# bot_schem_rev1.net
KiCad netlist of a schematic drawn in Altium Designer
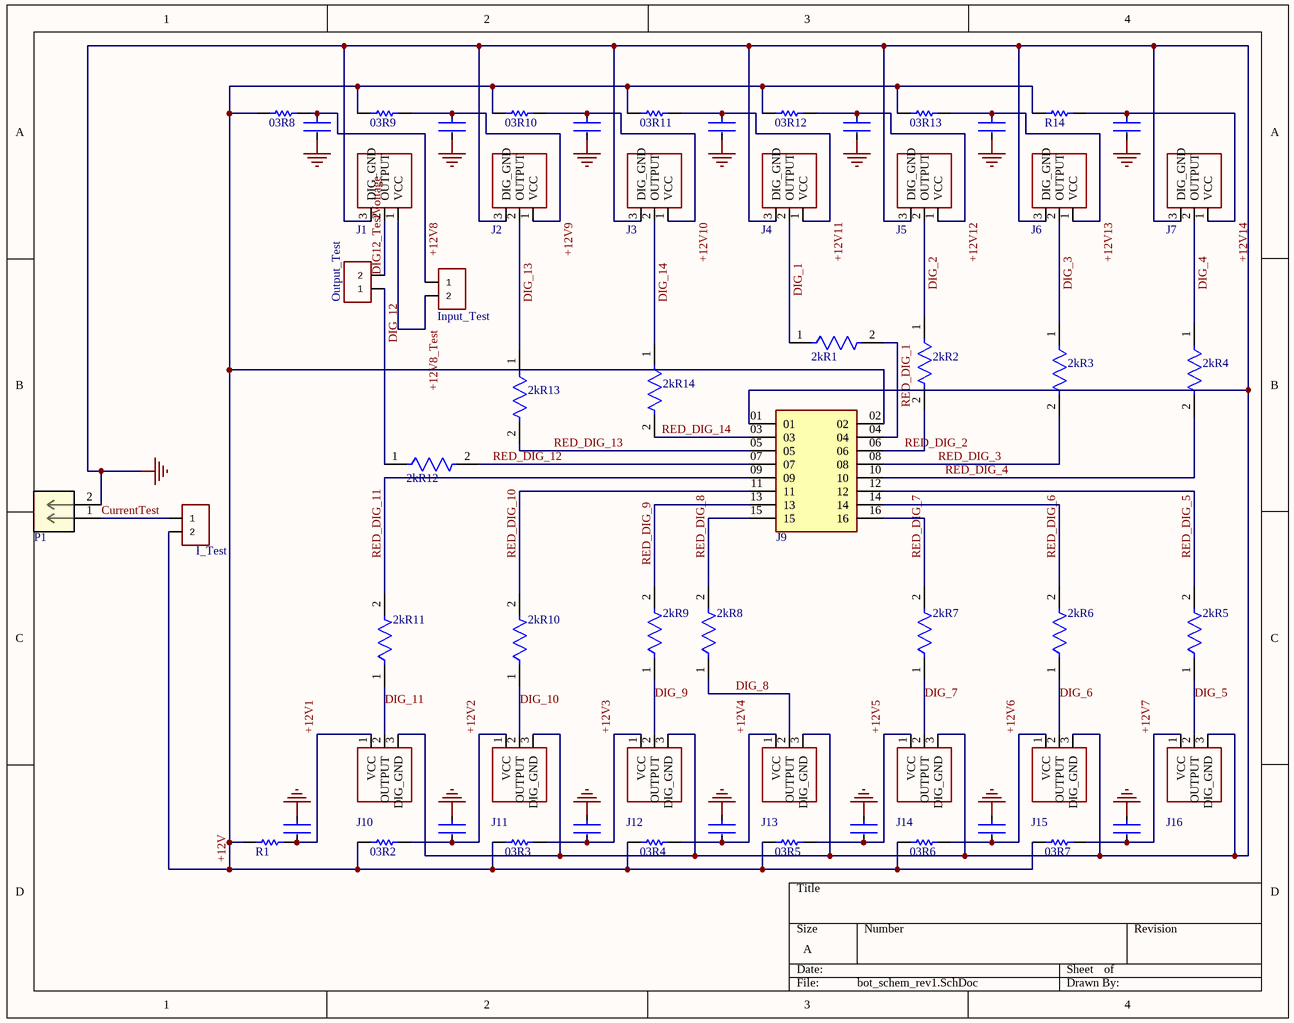
[diagram p0: bot_schem_rev1.SchDoc]

(export (version "E")
  (design (tool "Eeschema 10.0.6"))
  (components
    (comp (ref "2kR1")
      (value "CRCW06031K80FKEA")
      (footprint "2kOhm")
      (description "Res Thick Film 0603 1.8K Ohm 1% 1/10W ±100ppm/°C Molded SMD Paper T/R")
      (fields (field (name "MANUFACTURER") "Vishay") (field (name "TOLERANCE") "1%"))
      (libsource (lib "ps_schlib") (part "CRCW06031K80FKEA"))
    )
    (comp (ref "2kR2")
      (value "CRCW06031K80FKEA")
      (footprint "2kOhm")
      (description "Res Thick Film 0603 1.8K Ohm 1% 1/10W ±100ppm/°C Molded SMD Paper T/R")
      (fields (field (name "MANUFACTURER") "Vishay") (field (name "TOLERANCE") "1%"))
      (libsource (lib "ps_schlib") (part "CRCW06031K80FKEA"))
    )
    (comp (ref "2kR3")
      (value "CRCW06031K80FKEA")
      (footprint "2kOhm")
      (description "Res Thick Film 0603 1.8K Ohm 1% 1/10W ±100ppm/°C Molded SMD Paper T/R")
      (fields (field (name "MANUFACTURER") "Vishay") (field (name "TOLERANCE") "1%"))
      (libsource (lib "ps_schlib") (part "CRCW06031K80FKEA"))
    )
    (comp (ref "2kR4")
      (value "CRCW06031K80FKEA")
      (footprint "2kOhm")
      (description "Res Thick Film 0603 1.8K Ohm 1% 1/10W ±100ppm/°C Molded SMD Paper T/R")
      (fields (field (name "MANUFACTURER") "Vishay") (field (name "TOLERANCE") "1%"))
      (libsource (lib "ps_schlib") (part "CRCW06031K80FKEA"))
    )
    (comp (ref "2kR5")
      (value "CRCW06031K80FKEA")
      (footprint "2kOhm")
      (description "Res Thick Film 0603 1.8K Ohm 1% 1/10W ±100ppm/°C Molded SMD Paper T/R")
      (fields (field (name "MANUFACTURER") "Vishay") (field (name "TOLERANCE") "1%"))
      (libsource (lib "ps_schlib") (part "CRCW06031K80FKEA"))
    )
    (comp (ref "2kR6")
      (value "CRCW06031K80FKEA")
      (footprint "2kOhm")
      (description "Res Thick Film 0603 1.8K Ohm 1% 1/10W ±100ppm/°C Molded SMD Paper T/R")
      (fields (field (name "MANUFACTURER") "Vishay") (field (name "TOLERANCE") "1%"))
      (libsource (lib "ps_schlib") (part "CRCW06031K80FKEA"))
    )
    (comp (ref "2kR7")
      (value "CRCW06031K80FKEA")
      (footprint "2kOhm")
      (description "Res Thick Film 0603 1.8K Ohm 1% 1/10W ±100ppm/°C Molded SMD Paper T/R")
      (fields (field (name "MANUFACTURER") "Vishay") (field (name "TOLERANCE") "1%"))
      (libsource (lib "ps_schlib") (part "CRCW06031K80FKEA"))
    )
    (comp (ref "2kR8")
      (value "CRCW06031K80FKEA")
      (footprint "2kOhm")
      (description "Res Thick Film 0603 1.8K Ohm 1% 1/10W ±100ppm/°C Molded SMD Paper T/R")
      (fields (field (name "MANUFACTURER") "Vishay") (field (name "TOLERANCE") "1%"))
      (libsource (lib "ps_schlib") (part "CRCW06031K80FKEA"))
    )
    (comp (ref "2kR9")
      (value "CRCW06031K80FKEA")
      (footprint "2kOhm")
      (description "Res Thick Film 0603 1.8K Ohm 1% 1/10W ±100ppm/°C Molded SMD Paper T/R")
      (fields (field (name "MANUFACTURER") "Vishay") (field (name "TOLERANCE") "1%"))
      (libsource (lib "ps_schlib") (part "CRCW06031K80FKEA"))
    )
    (comp (ref "2kR10")
      (value "CRCW06031K80FKEA")
      (footprint "2kOhm")
      (description "Res Thick Film 0603 1.8K Ohm 1% 1/10W ±100ppm/°C Molded SMD Paper T/R")
      (fields (field (name "MANUFACTURER") "Vishay") (field (name "TOLERANCE") "1%"))
      (libsource (lib "ps_schlib") (part "CRCW06031K80FKEA"))
    )
    (comp (ref "2kR11")
      (value "CRCW06031K80FKEA")
      (footprint "2kOhm")
      (description "Res Thick Film 0603 1.8K Ohm 1% 1/10W ±100ppm/°C Molded SMD Paper T/R")
      (fields (field (name "MANUFACTURER") "Vishay") (field (name "TOLERANCE") "1%"))
      (libsource (lib "ps_schlib") (part "CRCW06031K80FKEA"))
    )
    (comp (ref "2kR12")
      (value "CRCW06031K80FKEA")
      (footprint "2kOhm")
      (description "Res Thick Film 0603 1.8K Ohm 1% 1/10W ±100ppm/°C Molded SMD Paper T/R")
      (fields (field (name "MANUFACTURER") "Vishay") (field (name "TOLERANCE") "1%"))
      (libsource (lib "ps_schlib") (part "CRCW06031K80FKEA"))
    )
    (comp (ref "2kR13")
      (value "CRCW06031K80FKEA")
      (footprint "2kOhm")
      (description "Res Thick Film 0603 1.8K Ohm 1% 1/10W ±100ppm/°C Molded SMD Paper T/R")
      (fields (field (name "MANUFACTURER") "Vishay") (field (name "TOLERANCE") "1%"))
      (libsource (lib "ps_schlib") (part "CRCW06031K80FKEA"))
    )
    (comp (ref "2kR14")
      (value "CRCW06031K80FKEA")
      (footprint "2kOhm")
      (description "Res Thick Film 0603 1.8K Ohm 1% 1/10W ±100ppm/°C Molded SMD Paper T/R")
      (fields (field (name "MANUFACTURER") "Vishay") (field (name "TOLERANCE") "1%"))
      (libsource (lib "ps_schlib") (part "CRCW06031K80FKEA"))
    )
    (comp (ref "03R2")
      (value "ERJ-2BQJR30X")
      (footprint "03 Ohm")
      (description "RES 0.3 OHM 5% 1/6W 0402")
      (fields (field (name "MANUFACTURER") "Panasonic") (field (name "TOLERANCE") "5%"))
      (libsource (lib "ps_schlib") (part "ERJ-2BQJR30X"))
    )
    (comp (ref "03R3")
      (value "ERJ-2BQJR30X")
      (footprint "03 Ohm")
      (description "RES 0.3 OHM 5% 1/6W 0402")
      (fields (field (name "MANUFACTURER") "Panasonic") (field (name "TOLERANCE") "5%"))
      (libsource (lib "ps_schlib") (part "ERJ-2BQJR30X"))
    )
    (comp (ref "03R4")
      (value "ERJ-2BQJR30X")
      (footprint "03 Ohm")
      (description "RES 0.3 OHM 5% 1/6W 0402")
      (fields (field (name "MANUFACTURER") "Panasonic") (field (name "TOLERANCE") "5%"))
      (libsource (lib "ps_schlib") (part "ERJ-2BQJR30X"))
    )
    (comp (ref "03R5")
      (value "ERJ-2BQJR30X")
      (footprint "03 Ohm")
      (description "RES 0.3 OHM 5% 1/6W 0402")
      (fields (field (name "MANUFACTURER") "Panasonic") (field (name "TOLERANCE") "5%"))
      (libsource (lib "ps_schlib") (part "ERJ-2BQJR30X"))
    )
    (comp (ref "03R6")
      (value "ERJ-2BQJR30X")
      (footprint "03 Ohm")
      (description "RES 0.3 OHM 5% 1/6W 0402")
      (fields (field (name "MANUFACTURER") "Panasonic") (field (name "TOLERANCE") "5%"))
      (libsource (lib "ps_schlib") (part "ERJ-2BQJR30X"))
    )
    (comp (ref "03R7")
      (value "ERJ-2BQJR30X")
      (footprint "03 Ohm")
      (description "RES 0.3 OHM 5% 1/6W 0402")
      (fields (field (name "MANUFACTURER") "Panasonic") (field (name "TOLERANCE") "5%"))
      (libsource (lib "ps_schlib") (part "ERJ-2BQJR30X"))
    )
    (comp (ref "03R8")
      (value "ERJ-2BQJR30X")
      (footprint "03 Ohm")
      (description "RES 0.3 OHM 5% 1/6W 0402")
      (fields (field (name "MANUFACTURER") "Panasonic") (field (name "TOLERANCE") "5%"))
      (libsource (lib "ps_schlib") (part "ERJ-2BQJR30X"))
    )
    (comp (ref "03R9")
      (value "ERJ-2BQJR30X")
      (footprint "03 Ohm")
      (description "RES 0.3 OHM 5% 1/6W 0402")
      (fields (field (name "MANUFACTURER") "Panasonic") (field (name "TOLERANCE") "5%"))
      (libsource (lib "ps_schlib") (part "ERJ-2BQJR30X"))
    )
    (comp (ref "03R10")
      (value "ERJ-2BQJR30X")
      (footprint "03 Ohm")
      (description "RES 0.3 OHM 5% 1/6W 0402")
      (fields (field (name "MANUFACTURER") "Panasonic") (field (name "TOLERANCE") "5%"))
      (libsource (lib "ps_schlib") (part "ERJ-2BQJR30X"))
    )
    (comp (ref "03R11")
      (value "ERJ-2BQJR30X")
      (footprint "03 Ohm")
      (description "RES 0.3 OHM 5% 1/6W 0402")
      (fields (field (name "MANUFACTURER") "Panasonic") (field (name "TOLERANCE") "5%"))
      (libsource (lib "ps_schlib") (part "ERJ-2BQJR30X"))
    )
    (comp (ref "03R12")
      (value "ERJ-2BQJR30X")
      (footprint "03 Ohm")
      (description "RES 0.3 OHM 5% 1/6W 0402")
      (fields (field (name "MANUFACTURER") "Panasonic") (field (name "TOLERANCE") "5%"))
      (libsource (lib "ps_schlib") (part "ERJ-2BQJR30X"))
    )
    (comp (ref "03R13")
      (value "ERJ-2BQJR30X")
      (footprint "03 Ohm")
      (description "RES 0.3 OHM 5% 1/6W 0402")
      (fields (field (name "MANUFACTURER") "Panasonic") (field (name "TOLERANCE") "5%"))
      (libsource (lib "ps_schlib") (part "ERJ-2BQJR30X"))
    )
    (comp (ref "100nF1")
      (value "C0805C104K5RACTU")
      (footprint "100nF")
      (description "Cap Ceramic 0.1uF 50V X7R 10% SMD 2.0 x 1.2 mm 125 C Paper T/R")
      (fields (field (name "MANUFACTURER") "KEMET") (field (name "TOLERANCE") "10%"))
      (libsource (lib "ps_schlib") (part "C0805C104K5RACTU"))
    )
    (comp (ref "100nF2")
      (value "C0805C104K5RACTU")
      (footprint "100nF")
      (description "Cap Ceramic 0.1uF 50V X7R 10% SMD 2.0 x 1.2 mm 125 C Paper T/R")
      (fields (field (name "MANUFACTURER") "KEMET") (field (name "TOLERANCE") "10%"))
      (libsource (lib "ps_schlib") (part "C0805C104K5RACTU"))
    )
    (comp (ref "100nF3")
      (value "C0805C104K5RACTU")
      (footprint "100nF")
      (description "Cap Ceramic 0.1uF 50V X7R 10% SMD 2.0 x 1.2 mm 125 C Paper T/R")
      (fields (field (name "MANUFACTURER") "KEMET") (field (name "TOLERANCE") "10%"))
      (libsource (lib "ps_schlib") (part "C0805C104K5RACTU"))
    )
    (comp (ref "100nF4")
      (value "C0805C104K5RACTU")
      (footprint "100nF")
      (description "Cap Ceramic 0.1uF 50V X7R 10% SMD 2.0 x 1.2 mm 125 C Paper T/R")
      (fields (field (name "MANUFACTURER") "KEMET") (field (name "TOLERANCE") "10%"))
      (libsource (lib "ps_schlib") (part "C0805C104K5RACTU"))
    )
    (comp (ref "100nF5")
      (value "C0805C104K5RACTU")
      (footprint "100nF")
      (description "Cap Ceramic 0.1uF 50V X7R 10% SMD 2.0 x 1.2 mm 125 C Paper T/R")
      (fields (field (name "MANUFACTURER") "KEMET") (field (name "TOLERANCE") "10%"))
      (libsource (lib "ps_schlib") (part "C0805C104K5RACTU"))
    )
    (comp (ref "100nF6")
      (value "C0805C104K5RACTU")
      (footprint "100nF")
      (description "Cap Ceramic 0.1uF 50V X7R 10% SMD 2.0 x 1.2 mm 125 C Paper T/R")
      (fields (field (name "MANUFACTURER") "KEMET") (field (name "TOLERANCE") "10%"))
      (libsource (lib "ps_schlib") (part "C0805C104K5RACTU"))
    )
    (comp (ref "100nF7")
      (value "C0805C104K5RACTU")
      (footprint "100nF")
      (description "Cap Ceramic 0.1uF 50V X7R 10% SMD 2.0 x 1.2 mm 125 C Paper T/R")
      (fields (field (name "MANUFACTURER") "KEMET") (field (name "TOLERANCE") "10%"))
      (libsource (lib "ps_schlib") (part "C0805C104K5RACTU"))
    )
    (comp (ref "100nF8")
      (value "C0805C104K5RACTU")
      (footprint "100nF")
      (description "Cap Ceramic 0.1uF 50V X7R 10% SMD 2.0 x 1.2 mm 125 C Paper T/R")
      (fields (field (name "MANUFACTURER") "KEMET") (field (name "TOLERANCE") "10%"))
      (libsource (lib "ps_schlib") (part "C0805C104K5RACTU"))
    )
    (comp (ref "100nF9")
      (value "C0805C104K5RACTU")
      (footprint "100nF")
      (description "Cap Ceramic 0.1uF 50V X7R 10% SMD 2.0 x 1.2 mm 125 C Paper T/R")
      (fields (field (name "MANUFACTURER") "KEMET") (field (name "TOLERANCE") "10%"))
      (libsource (lib "ps_schlib") (part "C0805C104K5RACTU"))
    )
    (comp (ref "100nF10")
      (value "C0805C104K5RACTU")
      (footprint "100nF")
      (description "Cap Ceramic 0.1uF 50V X7R 10% SMD 2.0 x 1.2 mm 125 C Paper T/R")
      (fields (field (name "MANUFACTURER") "KEMET") (field (name "TOLERANCE") "10%"))
      (libsource (lib "ps_schlib") (part "C0805C104K5RACTU"))
    )
    (comp (ref "100nF11")
      (value "C0805C104K5RACTU")
      (footprint "100nF")
      (description "Cap Ceramic 0.1uF 50V X7R 10% SMD 2.0 x 1.2 mm 125 C Paper T/R")
      (fields (field (name "MANUFACTURER") "KEMET") (field (name "TOLERANCE") "10%"))
      (libsource (lib "ps_schlib") (part "C0805C104K5RACTU"))
    )
    (comp (ref "100nF12")
      (value "C0805C104K5RACTU")
      (footprint "100nF")
      (description "Cap Ceramic 0.1uF 50V X7R 10% SMD 2.0 x 1.2 mm 125 C Paper T/R")
      (fields (field (name "MANUFACTURER") "KEMET") (field (name "TOLERANCE") "10%"))
      (libsource (lib "ps_schlib") (part "C0805C104K5RACTU"))
    )
    (comp (ref "100nF13")
      (value "C0805C104K5RACTU")
      (footprint "100nF")
      (description "Cap Ceramic 0.1uF 50V X7R 10% SMD 2.0 x 1.2 mm 125 C Paper T/R")
      (fields (field (name "MANUFACTURER") "KEMET") (field (name "TOLERANCE") "10%"))
      (libsource (lib "ps_schlib") (part "C0805C104K5RACTU"))
    )
    (comp (ref "100nF14")
      (value "C0805C104K5RACTU")
      (footprint "100nF")
      (description "Cap Ceramic 0.1uF 50V X7R 10% SMD 2.0 x 1.2 mm 125 C Paper T/R")
      (fields (field (name "MANUFACTURER") "KEMET") (field (name "TOLERANCE") "10%"))
      (libsource (lib "ps_schlib") (part "C0805C104K5RACTU"))
    )
    (comp (ref "Input_Test")
      (value "PRPC001DFAN-RC")
      (footprint "PRPC001DFAN-RC")
      (description "Conn Header Vert 2POS")
      (fields (field (name "MANUFACTURER") "Sullins"))
      (libsource (lib "ps_schlib") (part "PRPC001DFAN-RC"))
    )
    (comp (ref "I_Test")
      (value "PRPC001DFAN-RC")
      (footprint "PRPC001DFAN-RC")
      (description "Conn Header Vert 2POS")
      (fields (field (name "MANUFACTURER") "Sullins"))
      (libsource (lib "ps_schlib") (part "PRPC001DFAN-RC"))
    )
    (comp (ref "J1")
      (value "IF-D95T")
      (footprint "IF-D95")
      (description "DETECTOR PHOTOLOGIC TTL/CMOS")
      (fields (field (name "MANUFACTURER") "Industrial Fiber Optics"))
      (libsource (lib "ps_schlib") (part "IF-D95T"))
    )
    (comp (ref "J2")
      (value "IF-D95T")
      (footprint "IF-D95")
      (description "DETECTOR PHOTOLOGIC TTL/CMOS")
      (fields (field (name "MANUFACTURER") "Industrial Fiber Optics"))
      (libsource (lib "ps_schlib") (part "IF-D95T"))
    )
    (comp (ref "J3")
      (value "IF-D95T")
      (footprint "IF-D95")
      (description "DETECTOR PHOTOLOGIC TTL/CMOS")
      (fields (field (name "MANUFACTURER") "Industrial Fiber Optics"))
      (libsource (lib "ps_schlib") (part "IF-D95T"))
    )
    (comp (ref "J4")
      (value "IF-D95T")
      (footprint "IF-D95")
      (description "DETECTOR PHOTOLOGIC TTL/CMOS")
      (fields (field (name "MANUFACTURER") "Industrial Fiber Optics"))
      (libsource (lib "ps_schlib") (part "IF-D95T"))
    )
    (comp (ref "J5")
      (value "IF-D95T")
      (footprint "IF-D95")
      (description "DETECTOR PHOTOLOGIC TTL/CMOS")
      (fields (field (name "MANUFACTURER") "Industrial Fiber Optics"))
      (libsource (lib "ps_schlib") (part "IF-D95T"))
    )
    (comp (ref "J6")
      (value "IF-D95T")
      (footprint "IF-D95")
      (description "DETECTOR PHOTOLOGIC TTL/CMOS")
      (fields (field (name "MANUFACTURER") "Industrial Fiber Optics"))
      (libsource (lib "ps_schlib") (part "IF-D95T"))
    )
    (comp (ref "J7")
      (value "IF-D95T")
      (footprint "IF-D95")
      (description "DETECTOR PHOTOLOGIC TTL/CMOS")
      (fields (field (name "MANUFACTURER") "Industrial Fiber Optics"))
      (libsource (lib "ps_schlib") (part "IF-D95T"))
    )
    (comp (ref "J9")
      (value "HW-08-11-F-D-511-SM")
      (footprint "16 pin receiver")
      (libsource (lib "ps_schlib") (part "HW-08-11-F-D-507-SM"))
    )
    (comp (ref "J10")
      (value "IF-D95T")
      (footprint "IF-D95")
      (description "DETECTOR PHOTOLOGIC TTL/CMOS")
      (fields (field (name "MANUFACTURER") "Industrial Fiber Optics"))
      (libsource (lib "ps_schlib") (part "IF-D95T"))
    )
    (comp (ref "J11")
      (value "IF-D95T")
      (footprint "IF-D95")
      (description "DETECTOR PHOTOLOGIC TTL/CMOS")
      (fields (field (name "MANUFACTURER") "Industrial Fiber Optics"))
      (libsource (lib "ps_schlib") (part "IF-D95T"))
    )
    (comp (ref "J12")
      (value "IF-D95T")
      (footprint "IF-D95")
      (description "DETECTOR PHOTOLOGIC TTL/CMOS")
      (fields (field (name "MANUFACTURER") "Industrial Fiber Optics"))
      (libsource (lib "ps_schlib") (part "IF-D95T"))
    )
    (comp (ref "J13")
      (value "IF-D95T")
      (footprint "IF-D95")
      (description "DETECTOR PHOTOLOGIC TTL/CMOS")
      (fields (field (name "MANUFACTURER") "Industrial Fiber Optics"))
      (libsource (lib "ps_schlib") (part "IF-D95T"))
    )
    (comp (ref "J14")
      (value "IF-D95T")
      (footprint "IF-D95")
      (description "DETECTOR PHOTOLOGIC TTL/CMOS")
      (fields (field (name "MANUFACTURER") "Industrial Fiber Optics"))
      (libsource (lib "ps_schlib") (part "IF-D95T"))
    )
    (comp (ref "J15")
      (value "IF-D95T")
      (footprint "IF-D95")
      (description "DETECTOR PHOTOLOGIC TTL/CMOS")
      (fields (field (name "MANUFACTURER") "Industrial Fiber Optics"))
      (libsource (lib "ps_schlib") (part "IF-D95T"))
    )
    (comp (ref "J16")
      (value "IF-D95T")
      (footprint "IF-D95")
      (description "DETECTOR PHOTOLOGIC TTL/CMOS")
      (fields (field (name "MANUFACTURER") "Industrial Fiber Optics"))
      (libsource (lib "ps_schlib") (part "IF-D95T"))
    )
    (comp (ref "Output_Test")
      (value "PRPC001DFAN-RC")
      (footprint "PRPC001DFAN-RC")
      (description "Conn Header Vert 2POS")
      (fields (field (name "MANUFACTURER") "Sullins"))
      (libsource (lib "ps_schlib") (part "PRPC001DFAN-RC"))
    )
    (comp (ref "P1")
      (value "1054311102")
      (footprint "CONN_1054311102_MOL")
      (fields (field (name "MANUFACTURER") "Molex"))
      (libsource (lib "ps_schlib") (part "1054311102"))
    )
    (comp (ref "R1")
      (value "ERJ-2BQJR30X")
      (footprint "03 Ohm")
      (description "RES 0.3 OHM 5% 1/6W 0402")
      (fields (field (name "MANUFACTURER") "Panasonic") (field (name "TOLERANCE") "5%"))
      (libsource (lib "ps_schlib") (part "ERJ-2BQJR30X"))
    )
    (comp (ref "R14")
      (value "ERJ-2BQJR30X")
      (footprint "03 Ohm")
      (description "RES 0.3 OHM 5% 1/6W 0402")
      (fields (field (name "MANUFACTURER") "Panasonic") (field (name "TOLERANCE") "5%"))
      (libsource (lib "ps_schlib") (part "ERJ-2BQJR30X"))
    )
  )
  (nets
    (net (code "1") (name "/+12V") (class "Default")
      (node (ref "03R10") (pin "1") (pinfunction "1_1") (pintype "passive"))
      (node (ref "03R11") (pin "1") (pinfunction "1_1") (pintype "passive"))
      (node (ref "03R12") (pin "1") (pinfunction "1_1") (pintype "passive"))
      (node (ref "03R13") (pin "1") (pinfunction "1_1") (pintype "passive"))
      (node (ref "03R2") (pin "1") (pinfunction "1_1") (pintype "passive"))
      (node (ref "03R3") (pin "1") (pinfunction "1_1") (pintype "passive"))
      (node (ref "03R4") (pin "1") (pinfunction "1_1") (pintype "passive"))
      (node (ref "03R5") (pin "1") (pinfunction "1_1") (pintype "passive"))
      (node (ref "03R6") (pin "1") (pinfunction "1_1") (pintype "passive"))
      (node (ref "03R7") (pin "1") (pinfunction "1_1") (pintype "passive"))
      (node (ref "03R8") (pin "1") (pinfunction "1_1") (pintype "passive"))
      (node (ref "03R9") (pin "1") (pinfunction "1_1") (pintype "passive"))
      (node (ref "I_Test") (pin "2") (pinfunction "2_2") (pintype "passive"))
      (node (ref "J9") (pin "02") (pinfunction "02_02") (pintype "passive"))
      (node (ref "R1") (pin "1") (pinfunction "1_1") (pintype "passive"))
      (node (ref "R14") (pin "1") (pinfunction "1_1") (pintype "passive"))
    )
    (net (code "2") (name "/+12V1") (class "Default")
      (node (ref "100nF1") (pin "2") (pinfunction "2_2") (pintype "passive"))
      (node (ref "J10") (pin "1") (pinfunction "VCC_1") (pintype "passive"))
      (node (ref "R1") (pin "2") (pinfunction "2_2") (pintype "passive"))
    )
    (net (code "3") (name "/+12V2") (class "Default")
      (node (ref "03R2") (pin "2") (pinfunction "2_2") (pintype "passive"))
      (node (ref "100nF2") (pin "2") (pinfunction "2_2") (pintype "passive"))
      (node (ref "J11") (pin "1") (pinfunction "VCC_1") (pintype "passive"))
    )
    (net (code "4") (name "/+12V3") (class "Default")
      (node (ref "03R3") (pin "2") (pinfunction "2_2") (pintype "passive"))
      (node (ref "100nF3") (pin "2") (pinfunction "2_2") (pintype "passive"))
      (node (ref "J12") (pin "1") (pinfunction "VCC_1") (pintype "passive"))
    )
    (net (code "5") (name "/+12V4") (class "Default")
      (node (ref "03R4") (pin "2") (pinfunction "2_2") (pintype "passive"))
      (node (ref "100nF4") (pin "2") (pinfunction "2_2") (pintype "passive"))
      (node (ref "J13") (pin "1") (pinfunction "VCC_1") (pintype "passive"))
    )
    (net (code "6") (name "/+12V5") (class "Default")
      (node (ref "03R5") (pin "2") (pinfunction "2_2") (pintype "passive"))
      (node (ref "100nF5") (pin "2") (pinfunction "2_2") (pintype "passive"))
      (node (ref "J14") (pin "1") (pinfunction "VCC_1") (pintype "passive"))
    )
    (net (code "7") (name "/+12V6") (class "Default")
      (node (ref "03R6") (pin "2") (pinfunction "2_2") (pintype "passive"))
      (node (ref "100nF6") (pin "2") (pinfunction "2_2") (pintype "passive"))
      (node (ref "J15") (pin "1") (pinfunction "VCC_1") (pintype "passive"))
    )
    (net (code "8") (name "/+12V7") (class "Default")
      (node (ref "03R7") (pin "2") (pinfunction "2_2") (pintype "passive"))
      (node (ref "100nF7") (pin "2") (pinfunction "2_2") (pintype "passive"))
      (node (ref "J16") (pin "1") (pinfunction "VCC_1") (pintype "passive"))
    )
    (net (code "9") (name "/+12V8") (class "Default")
      (node (ref "03R8") (pin "2") (pinfunction "2_2") (pintype "passive"))
      (node (ref "100nF8") (pin "1") (pinfunction "1_1") (pintype "passive"))
      (node (ref "Input_Test") (pin "1") (pinfunction "1_1") (pintype "passive"))
    )
    (net (code "10") (name "/+12V8_Test") (class "Default")
      (node (ref "Input_Test") (pin "2") (pinfunction "2_2") (pintype "passive"))
      (node (ref "J1") (pin "1") (pinfunction "VCC_1") (pintype "passive"))
    )
    (net (code "11") (name "/+12V9") (class "Default")
      (node (ref "03R9") (pin "2") (pinfunction "2_2") (pintype "passive"))
      (node (ref "100nF9") (pin "1") (pinfunction "1_1") (pintype "passive"))
      (node (ref "J2") (pin "1") (pinfunction "VCC_1") (pintype "passive"))
    )
    (net (code "12") (name "/+12V10") (class "Default")
      (node (ref "03R10") (pin "2") (pinfunction "2_2") (pintype "passive"))
      (node (ref "100nF10") (pin "1") (pinfunction "1_1") (pintype "passive"))
      (node (ref "J3") (pin "1") (pinfunction "VCC_1") (pintype "passive"))
    )
    (net (code "13") (name "/+12V11") (class "Default")
      (node (ref "03R11") (pin "2") (pinfunction "2_2") (pintype "passive"))
      (node (ref "100nF11") (pin "1") (pinfunction "1_1") (pintype "passive"))
      (node (ref "J4") (pin "1") (pinfunction "VCC_1") (pintype "passive"))
    )
    (net (code "14") (name "/+12V12") (class "Default")
      (node (ref "03R12") (pin "2") (pinfunction "2_2") (pintype "passive"))
      (node (ref "100nF12") (pin "1") (pinfunction "1_1") (pintype "passive"))
      (node (ref "J5") (pin "1") (pinfunction "VCC_1") (pintype "passive"))
    )
    (net (code "15") (name "/+12V13") (class "Default")
      (node (ref "03R13") (pin "2") (pinfunction "2_2") (pintype "passive"))
      (node (ref "100nF13") (pin "1") (pinfunction "1_1") (pintype "passive"))
      (node (ref "J6") (pin "1") (pinfunction "VCC_1") (pintype "passive"))
    )
    (net (code "16") (name "/+12V14") (class "Default")
      (node (ref "100nF14") (pin "1") (pinfunction "1_1") (pintype "passive"))
      (node (ref "J7") (pin "1") (pinfunction "VCC_1") (pintype "passive"))
      (node (ref "R14") (pin "2") (pinfunction "2_2") (pintype "passive"))
    )
    (net (code "18") (name "/CurrentTest") (class "Default")
      (node (ref "I_Test") (pin "1") (pinfunction "1_1") (pintype "passive"))
      (node (ref "P1") (pin "1") (pinfunction "1_1") (pintype "passive"))
    )
    (net (code "19") (name "/DIG12_TestVoltage") (class "Default")
      (node (ref "J1") (pin "2") (pinfunction "OUTPUT_2") (pintype "passive"))
      (node (ref "Output_Test") (pin "2") (pinfunction "2_2") (pintype "passive"))
    )
    (net (code "20") (name "/DIG_1") (class "Default")
      (node (ref "2kR1") (pin "1") (pinfunction "1_1") (pintype "passive"))
      (node (ref "J4") (pin "2") (pinfunction "OUTPUT_2") (pintype "passive"))
    )
    (net (code "21") (name "/DIG_2") (class "Default")
      (node (ref "2kR2") (pin "1") (pinfunction "1_1") (pintype "passive"))
      (node (ref "J5") (pin "2") (pinfunction "OUTPUT_2") (pintype "passive"))
    )
    (net (code "22") (name "/DIG_3") (class "Default")
      (node (ref "2kR3") (pin "1") (pinfunction "1_1") (pintype "passive"))
      (node (ref "J6") (pin "2") (pinfunction "OUTPUT_2") (pintype "passive"))
    )
    (net (code "23") (name "/DIG_4") (class "Default")
      (node (ref "2kR4") (pin "1") (pinfunction "1_1") (pintype "passive"))
      (node (ref "J7") (pin "2") (pinfunction "OUTPUT_2") (pintype "passive"))
    )
    (net (code "24") (name "/DIG_5") (class "Default")
      (node (ref "2kR5") (pin "1") (pinfunction "1_1") (pintype "passive"))
      (node (ref "J16") (pin "2") (pinfunction "OUTPUT_2") (pintype "passive"))
    )
    (net (code "25") (name "/DIG_6") (class "Default")
      (node (ref "2kR6") (pin "1") (pinfunction "1_1") (pintype "passive"))
      (node (ref "J15") (pin "2") (pinfunction "OUTPUT_2") (pintype "passive"))
    )
    (net (code "26") (name "/DIG_7") (class "Default")
      (node (ref "2kR7") (pin "1") (pinfunction "1_1") (pintype "passive"))
      (node (ref "J14") (pin "2") (pinfunction "OUTPUT_2") (pintype "passive"))
    )
    (net (code "27") (name "/DIG_8") (class "Default")
      (node (ref "2kR8") (pin "1") (pinfunction "1_1") (pintype "passive"))
      (node (ref "J13") (pin "2") (pinfunction "OUTPUT_2") (pintype "passive"))
    )
    (net (code "28") (name "/DIG_9") (class "Default")
      (node (ref "2kR9") (pin "1") (pinfunction "1_1") (pintype "passive"))
      (node (ref "J12") (pin "2") (pinfunction "OUTPUT_2") (pintype "passive"))
    )
    (net (code "29") (name "/DIG_10") (class "Default")
      (node (ref "2kR10") (pin "1") (pinfunction "1_1") (pintype "passive"))
      (node (ref "J11") (pin "2") (pinfunction "OUTPUT_2") (pintype "passive"))
    )
    (net (code "30") (name "/DIG_11") (class "Default")
      (node (ref "2kR11") (pin "1") (pinfunction "1_1") (pintype "passive"))
      (node (ref "J10") (pin "2") (pinfunction "OUTPUT_2") (pintype "passive"))
    )
    (net (code "31") (name "/DIG_12") (class "Default")
      (node (ref "2kR12") (pin "1") (pinfunction "1_1") (pintype "passive"))
      (node (ref "Output_Test") (pin "1") (pinfunction "1_1") (pintype "passive"))
    )
    (net (code "32") (name "/DIG_13") (class "Default")
      (node (ref "2kR13") (pin "1") (pinfunction "1_1") (pintype "passive"))
      (node (ref "J2") (pin "2") (pinfunction "OUTPUT_2") (pintype "passive"))
    )
    (net (code "33") (name "/DIG_14") (class "Default")
      (node (ref "2kR14") (pin "1") (pinfunction "1_1") (pintype "passive"))
      (node (ref "J3") (pin "2") (pinfunction "OUTPUT_2") (pintype "passive"))
    )
    (net (code "34") (name "/RED_DIG_1") (class "Default")
      (node (ref "2kR1") (pin "2") (pinfunction "2_2") (pintype "passive"))
      (node (ref "J9") (pin "04") (pinfunction "04_04") (pintype "passive"))
    )
    (net (code "35") (name "/RED_DIG_2") (class "Default")
      (node (ref "2kR2") (pin "2") (pinfunction "2_2") (pintype "passive"))
      (node (ref "J9") (pin "06") (pinfunction "06_06") (pintype "passive"))
    )
    (net (code "36") (name "/RED_DIG_3") (class "Default")
      (node (ref "2kR3") (pin "2") (pinfunction "2_2") (pintype "passive"))
      (node (ref "J9") (pin "08") (pinfunction "08_08") (pintype "passive"))
    )
    (net (code "37") (name "/RED_DIG_4") (class "Default")
      (node (ref "2kR4") (pin "2") (pinfunction "2_2") (pintype "passive"))
      (node (ref "J9") (pin "10") (pinfunction "10_10") (pintype "passive"))
    )
    (net (code "38") (name "/RED_DIG_5") (class "Default")
      (node (ref "2kR5") (pin "2") (pinfunction "2_2") (pintype "passive"))
      (node (ref "J9") (pin "12") (pinfunction "12_12") (pintype "passive"))
    )
    (net (code "39") (name "/RED_DIG_6") (class "Default")
      (node (ref "2kR6") (pin "2") (pinfunction "2_2") (pintype "passive"))
      (node (ref "J9") (pin "14") (pinfunction "14_14") (pintype "passive"))
    )
    (net (code "40") (name "/RED_DIG_7") (class "Default")
      (node (ref "2kR7") (pin "2") (pinfunction "2_2") (pintype "passive"))
      (node (ref "J9") (pin "16") (pinfunction "16_16") (pintype "passive"))
    )
    (net (code "41") (name "/RED_DIG_8") (class "Default")
      (node (ref "2kR8") (pin "2") (pinfunction "2_2") (pintype "passive"))
      (node (ref "J9") (pin "15") (pinfunction "15_15") (pintype "passive"))
    )
    (net (code "42") (name "/RED_DIG_9") (class "Default")
      (node (ref "2kR9") (pin "2") (pinfunction "2_2") (pintype "passive"))
      (node (ref "J9") (pin "13") (pinfunction "13_13") (pintype "passive"))
    )
    (net (code "43") (name "/RED_DIG_10") (class "Default")
      (node (ref "2kR10") (pin "2") (pinfunction "2_2") (pintype "passive"))
      (node (ref "J9") (pin "11") (pinfunction "11_11") (pintype "passive"))
    )
    (net (code "44") (name "/RED_DIG_11") (class "Default")
      (node (ref "2kR11") (pin "2") (pinfunction "2_2") (pintype "passive"))
      (node (ref "J9") (pin "09") (pinfunction "09_09") (pintype "passive"))
    )
    (net (code "45") (name "/RED_DIG_12") (class "Default")
      (node (ref "2kR12") (pin "2") (pinfunction "2_2") (pintype "passive"))
      (node (ref "J9") (pin "07") (pinfunction "07_07") (pintype "passive"))
    )
    (net (code "46") (name "/RED_DIG_13") (class "Default")
      (node (ref "2kR13") (pin "2") (pinfunction "2_2") (pintype "passive"))
      (node (ref "J9") (pin "05") (pinfunction "05_05") (pintype "passive"))
    )
    (net (code "47") (name "/RED_DIG_14") (class "Default")
      (node (ref "2kR14") (pin "2") (pinfunction "2_2") (pintype "passive"))
      (node (ref "J9") (pin "03") (pinfunction "03_03") (pintype "passive"))
    )
    (net (code "48") (name "GND") (class "Default")
      (node (ref "100nF1") (pin "1") (pinfunction "1_1") (pintype "passive"))
      (node (ref "100nF10") (pin "2") (pinfunction "2_2") (pintype "passive"))
      (node (ref "100nF11") (pin "2") (pinfunction "2_2") (pintype "passive"))
      (node (ref "100nF12") (pin "2") (pinfunction "2_2") (pintype "passive"))
      (node (ref "100nF13") (pin "2") (pinfunction "2_2") (pintype "passive"))
      (node (ref "100nF14") (pin "2") (pinfunction "2_2") (pintype "passive"))
      (node (ref "100nF2") (pin "1") (pinfunction "1_1") (pintype "passive"))
      (node (ref "100nF3") (pin "1") (pinfunction "1_1") (pintype "passive"))
      (node (ref "100nF4") (pin "1") (pinfunction "1_1") (pintype "passive"))
      (node (ref "100nF5") (pin "1") (pinfunction "1_1") (pintype "passive"))
      (node (ref "100nF6") (pin "1") (pinfunction "1_1") (pintype "passive"))
      (node (ref "100nF7") (pin "1") (pinfunction "1_1") (pintype "passive"))
      (node (ref "100nF8") (pin "2") (pinfunction "2_2") (pintype "passive"))
      (node (ref "100nF9") (pin "2") (pinfunction "2_2") (pintype "passive"))
      (node (ref "J1") (pin "3") (pinfunction "DIG_GND_3") (pintype "passive"))
      (node (ref "J10") (pin "3") (pinfunction "DIG_GND_3") (pintype "passive"))
      (node (ref "J11") (pin "3") (pinfunction "DIG_GND_3") (pintype "passive"))
      (node (ref "J12") (pin "3") (pinfunction "DIG_GND_3") (pintype "passive"))
      (node (ref "J13") (pin "3") (pinfunction "DIG_GND_3") (pintype "passive"))
      (node (ref "J14") (pin "3") (pinfunction "DIG_GND_3") (pintype "passive"))
      (node (ref "J15") (pin "3") (pinfunction "DIG_GND_3") (pintype "passive"))
      (node (ref "J16") (pin "3") (pinfunction "DIG_GND_3") (pintype "passive"))
      (node (ref "J2") (pin "3") (pinfunction "DIG_GND_3") (pintype "passive"))
      (node (ref "J3") (pin "3") (pinfunction "DIG_GND_3") (pintype "passive"))
      (node (ref "J4") (pin "3") (pinfunction "DIG_GND_3") (pintype "passive"))
      (node (ref "J5") (pin "3") (pinfunction "DIG_GND_3") (pintype "passive"))
      (node (ref "J6") (pin "3") (pinfunction "DIG_GND_3") (pintype "passive"))
      (node (ref "J7") (pin "3") (pinfunction "DIG_GND_3") (pintype "passive"))
      (node (ref "J9") (pin "01") (pinfunction "01_01") (pintype "passive"))
      (node (ref "P1") (pin "2") (pinfunction "2_2") (pintype "passive"))
    )
  )
)
